# Mega-NTP-GPS-Shieldv3.net
KiCad netlist of a schematic drawn in EAGLE
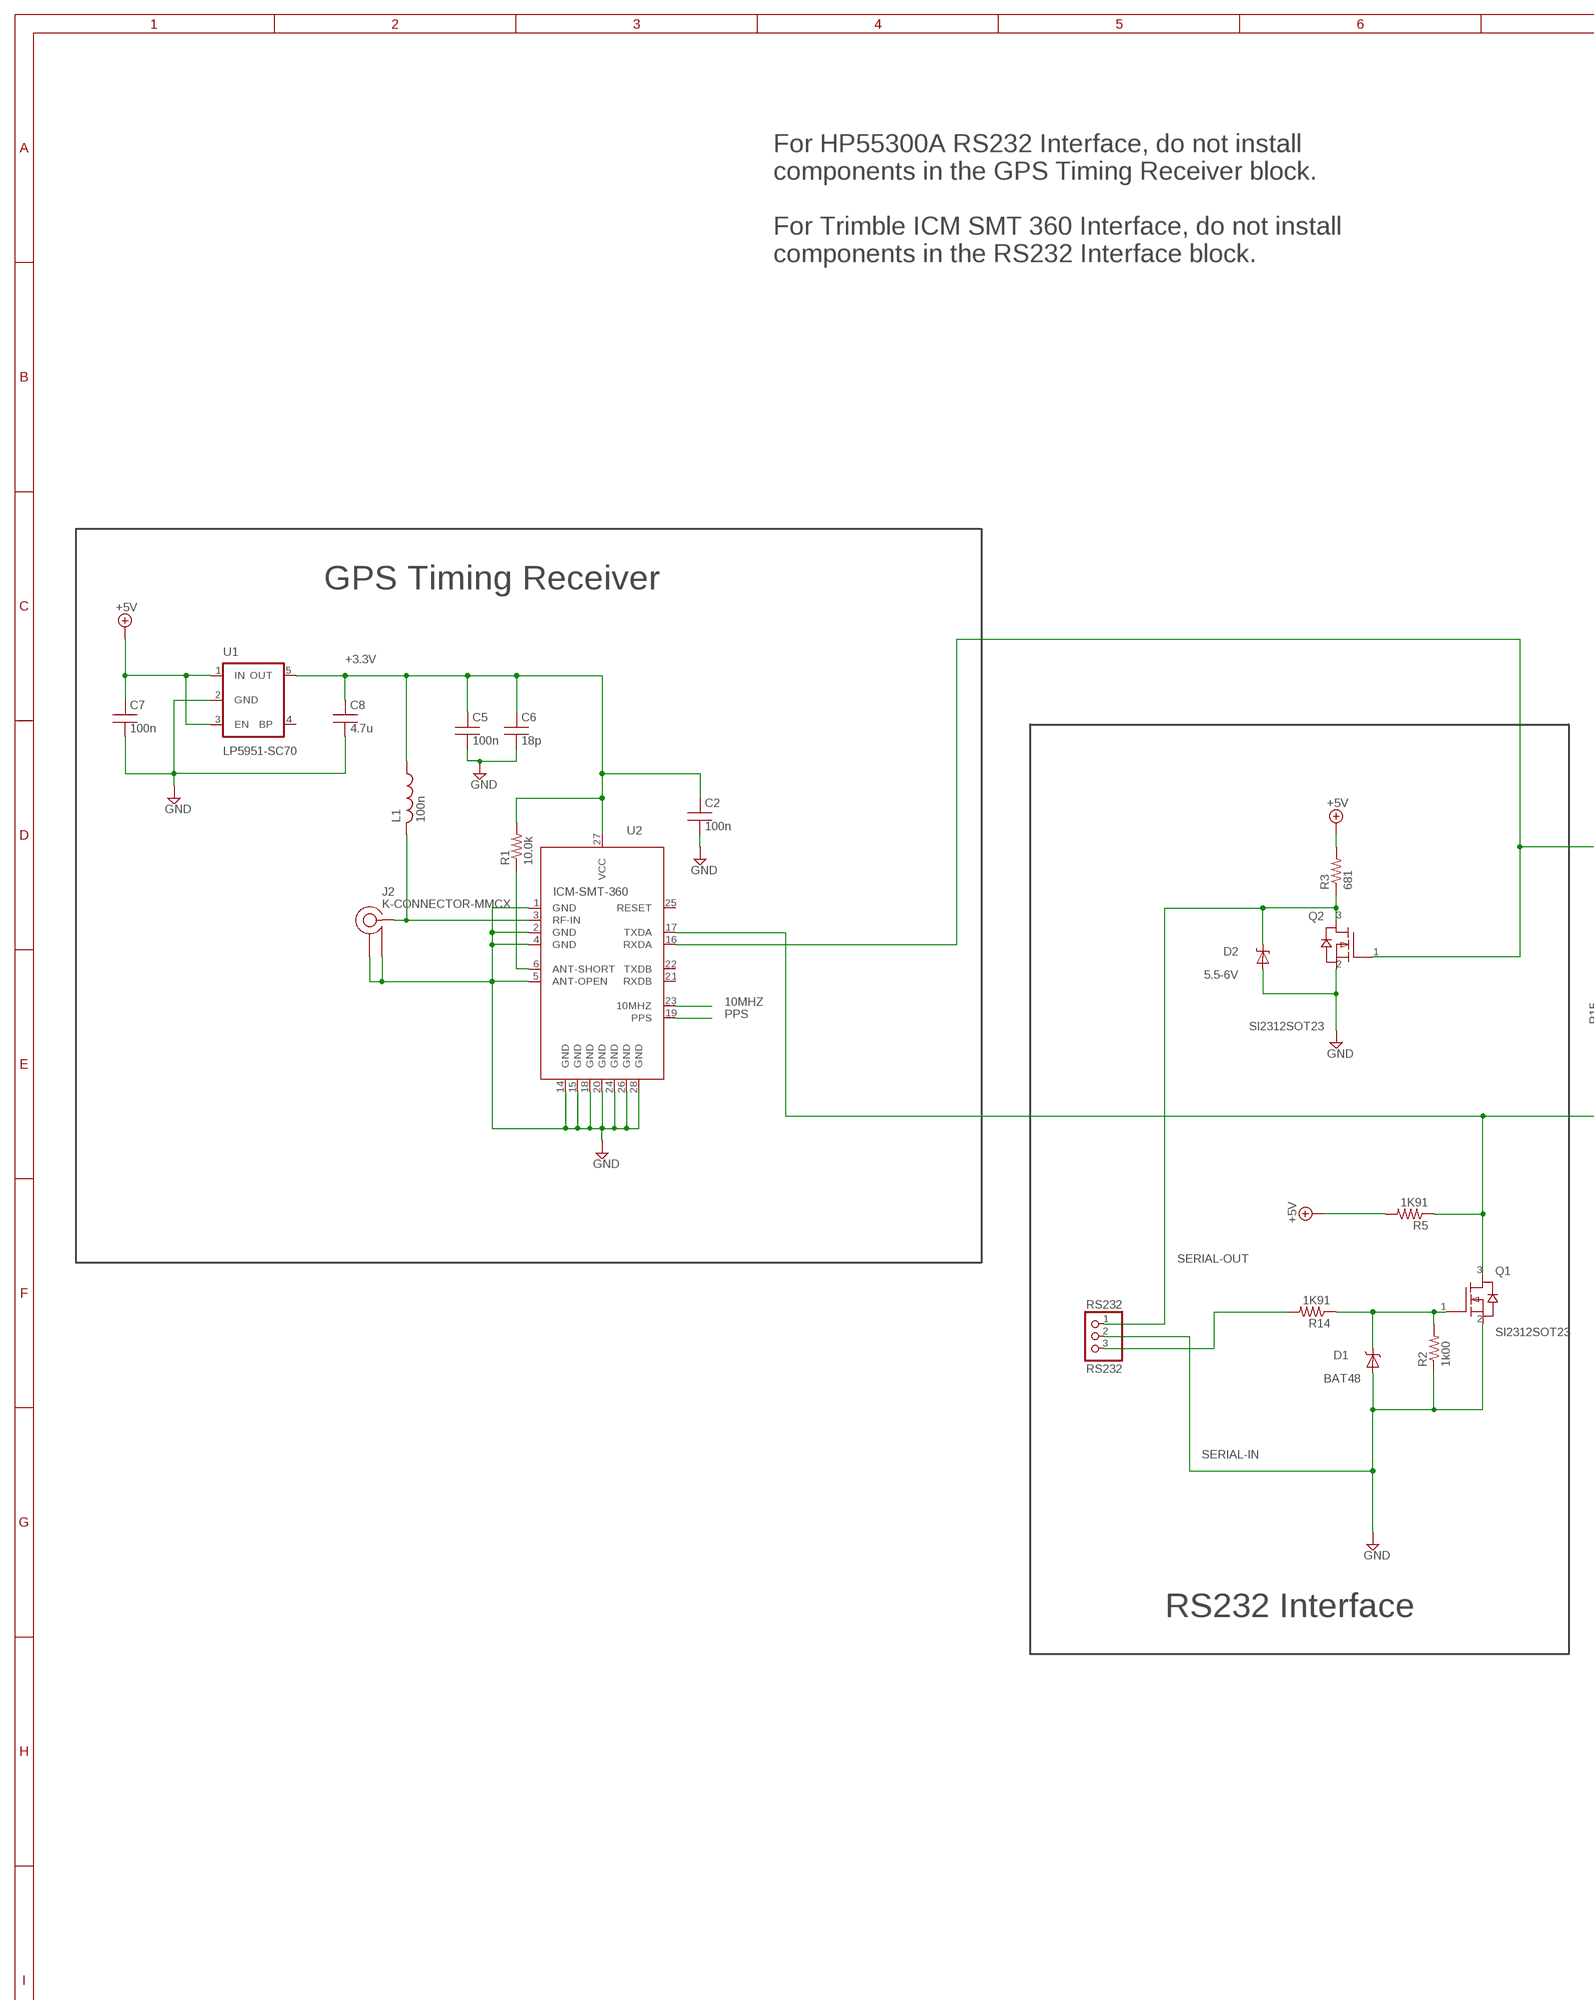
[diagram p0: schematic, sheet 1, part 1 of 2]
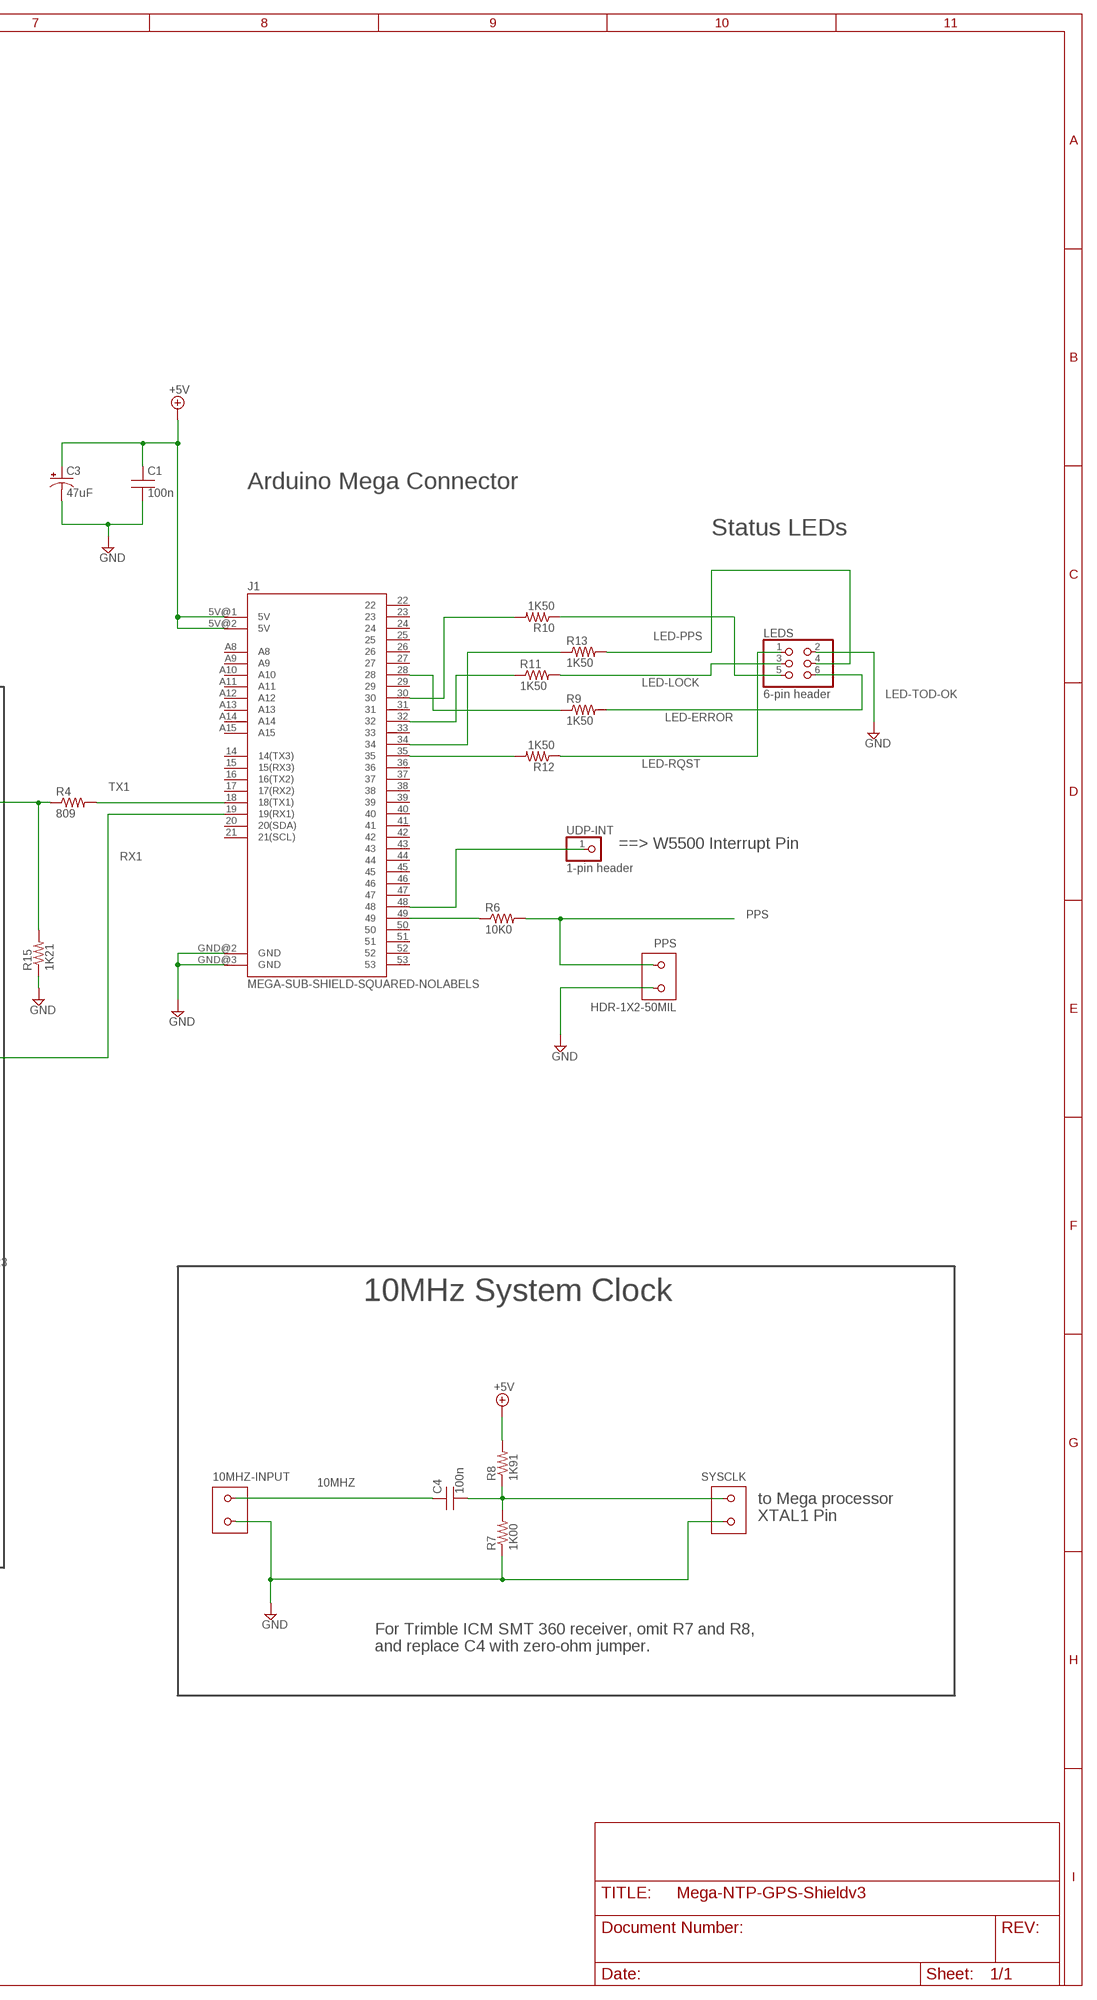
[diagram p1: schematic, sheet 1, part 2 of 2]

(export (version "E")
  (design (tool "Eeschema 10.0.6"))
  (components
    (comp (ref "10MHZ-INPUT")
      (value "HDR-1X2-100MIL")
      (footprint "eagle-import:1X02-100MIL")
      (libsource (lib "eagle-import") (part "HDR-1X2-100MIL"))
    )
    (comp (ref "C1")
      (value "100n")
      (footprint "eagle-import:AVX-0805")
      (fields (field (name "MFR") "AVX") (field (name "MPN") "0805(3/5)C104(J/K)ATxx"))
      (libsource (lib "eagle-import") (part "C-AVX-0805"))
    )
    (comp (ref "C2")
      (value "100n")
      (footprint "eagle-import:AVX-0805-NT")
      (fields (field (name "MFR") "AVX") (field (name "MPN") "0805(3/5)C104(J/K)ATxx"))
      (libsource (lib "eagle-import") (part "C-AVX-0805-NT"))
    )
    (comp (ref "C3")
      (value "47uF")
      (footprint "eagle-import:EIA3528")
      (fields (field (name "MFR") "Vishay/Sprague") (field (name "MPN") "TR3B476K010C0350"))
      (libsource (lib "eagle-import") (part "47UF-TANT"))
    )
    (comp (ref "C4")
      (value "100n")
      (footprint "eagle-import:AVX-0603")
      (fields (field (name "MFR") "AVX") (field (name "MPN") "0603(3/5)C104(J/K)ATxx"))
      (libsource (lib "eagle-import") (part "C-AVX-0603"))
    )
    (comp (ref "C5")
      (value "100n")
      (footprint "eagle-import:AVX-0603-NT")
      (fields (field (name "MFR") "AVX") (field (name "MPN") "0603(3/5)C104(J/K)ATxx"))
      (libsource (lib "eagle-import") (part "C-AVX-0603-NT"))
    )
    (comp (ref "C6")
      (value "18p")
      (footprint "eagle-import:AVX-0402-NT")
      (fields (field (name "MFR") "AVX") (field (name "MPN") "04025A180JATxx"))
      (libsource (lib "eagle-import") (part "C-AVX-0402-NT"))
    )
    (comp (ref "C7")
      (value "100n")
      (footprint "eagle-import:AVX-0603-NT")
      (fields (field (name "MFR") "AVX") (field (name "MPN") "0603(3/5)C104(J/K)ATxx"))
      (libsource (lib "eagle-import") (part "C-AVX-0603-NT"))
    )
    (comp (ref "C8")
      (value "4.7u")
      (footprint "eagle-import:AVX-0805-NT")
      (fields (field (name "MFR") "AVX") (field (name "MPN") "C0805YC475KATxx"))
      (libsource (lib "eagle-import") (part "C-AVX-0805-NT"))
    )
    (comp (ref "D1")
      (value "BAT48")
      (footprint "eagle-import:SOD-323")
      (libsource (lib "eagle-import") (part "DIODE-SCHOTTKY-SOD323"))
    )
    (comp (ref "D2")
      (value "5.5-6V")
      (footprint "eagle-import:SOD-323")
      (libsource (lib "eagle-import") (part "DIODE-ZENER-BZT52"))
    )
    (comp (ref "J1")
      (value "MEGA-SUB-SHIELD-SQUARED-NOLABELS")
      (footprint "eagle-import:MEGA-SUB-SHIELD-SQUARED-NOLABELS")
      (libsource (lib "eagle-import") (part "MEGA-SUB-SHIELD-SQUARED-NOLABELS"))
    )
    (comp (ref "J2")
      (value "K-CONNECTOR-MMCX")
      (footprint "eagle-import:MOLEX-MMCX-VERTICAL")
      (fields (field (name "MFR") "Molex") (field (name "MPN") "73415-206x"))
      (libsource (lib "eagle-import") (part "K-CONNECTOR-MMCX"))
    )
    (comp (ref "L1")
      (value "100n")
      (footprint "eagle-import:AVX-0603-NT")
      (fields (field (name "MFR") "Murata") (field (name "MPN") "LQW18ANR10J00"))
      (libsource (lib "eagle-import") (part "MURATA-LQW04A-LQW181-NT"))
    )
    (comp (ref "LEDS")
      (value "6-pin header")
      (footprint "eagle-import:2X03-50MIL")
      (libsource (lib "eagle-import") (part "HDR-2X3-ROW-SWAP-50MIL"))
    )
    (comp (ref "PPS")
      (value "HDR-1X2-50MIL")
      (footprint "eagle-import:1X02-50MIL")
      (libsource (lib "eagle-import") (part "HDR-1X2-50MIL"))
    )
    (comp (ref "Q1")
      (value "SI2312SOT23")
      (footprint "eagle-import:SOT23")
      (fields (field (name "MFR") "Siliconix") (field (name "MPN") "SI2312BDS"))
      (libsource (lib "eagle-import") (part "SI2312SOT23"))
    )
    (comp (ref "Q2")
      (value "SI2312SOT23")
      (footprint "eagle-import:SOT23")
      (fields (field (name "MFR") "Siliconix") (field (name "MPN") "SI2312BDS"))
      (libsource (lib "eagle-import") (part "SI2312SOT23"))
    )
    (comp (ref "R1")
      (value "10.0k")
      (footprint "eagle-import:AVX-0603")
      (fields (field (name "MFR") "Vishay/Dale") (field (name "MPN") "CRCW060310.0kFKxx"))
      (libsource (lib "eagle-import") (part "R-AVX-0603"))
    )
    (comp (ref "R2")
      (value "1k00")
      (footprint "eagle-import:AVX-0603-NT")
      (fields (field (name "MFR") "Vishay/Dale") (field (name "MPN") "CRCW06034K02FKxx"))
      (libsource (lib "eagle-import") (part "R-AVX-0603-NT"))
    )
    (comp (ref "R3")
      (value "681")
      (footprint "eagle-import:AVX-0603")
      (fields (field (name "MFR") "Vishay/Dale") (field (name "MPN") "CRCW0603DNP (681)FKxx"))
      (libsource (lib "eagle-import") (part "R-AVX-0603"))
    )
    (comp (ref "R4")
      (value "809")
      (footprint "eagle-import:AVX-0603")
      (fields (field (name "MFR") "Vishay/Dale") (field (name "MPN") "CRCW06031K91FKxx"))
      (libsource (lib "eagle-import") (part "R-AVX-0603"))
    )
    (comp (ref "R5")
      (value "1K91")
      (footprint "eagle-import:AVX-0603")
      (fields (field (name "MFR") "Vishay/Dale") (field (name "MPN") "CRCW06031K91FKxx"))
      (libsource (lib "eagle-import") (part "R-AVX-0603"))
    )
    (comp (ref "R6")
      (value "10K0")
      (footprint "eagle-import:AVX-0603")
      (fields (field (name "MFR") "Vishay/Dale") (field (name "MPN") "CRCW060310K0FKxx"))
      (libsource (lib "eagle-import") (part "R-AVX-0603"))
    )
    (comp (ref "R7")
      (value "1K00")
      (footprint "eagle-import:AVX-0603")
      (fields (field (name "MFR") "Vishay/Dale") (field (name "MPN") "CRCW06031K91FKxx"))
      (libsource (lib "eagle-import") (part "R-AVX-0603"))
    )
    (comp (ref "R8")
      (value "1K91")
      (footprint "eagle-import:AVX-0603")
      (fields (field (name "MFR") "Vishay/Dale") (field (name "MPN") "CRCW06031K91FKxx"))
      (libsource (lib "eagle-import") (part "R-AVX-0603"))
    )
    (comp (ref "R9")
      (value "1K50")
      (footprint "eagle-import:AVX-0603")
      (fields (field (name "MFR") "Vishay/Dale") (field (name "MPN") "CRCW06031K50FKxx"))
      (libsource (lib "eagle-import") (part "R-AVX-0603"))
    )
    (comp (ref "R10")
      (value "1K50")
      (footprint "eagle-import:AVX-0603")
      (fields (field (name "MFR") "Vishay/Dale") (field (name "MPN") "CRCW06031K50FKxx"))
      (libsource (lib "eagle-import") (part "R-AVX-0603"))
    )
    (comp (ref "R11")
      (value "1K50")
      (footprint "eagle-import:AVX-0603")
      (fields (field (name "MFR") "Vishay/Dale") (field (name "MPN") "CRCW06031K50FKxx"))
      (libsource (lib "eagle-import") (part "R-AVX-0603"))
    )
    (comp (ref "R12")
      (value "1K50")
      (footprint "eagle-import:AVX-0603")
      (fields (field (name "MFR") "Vishay/Dale") (field (name "MPN") "CRCW06031K50FKxx"))
      (libsource (lib "eagle-import") (part "R-AVX-0603"))
    )
    (comp (ref "R13")
      (value "1K50")
      (footprint "eagle-import:AVX-0603")
      (fields (field (name "MFR") "Vishay/Dale") (field (name "MPN") "CRCW06031K50FKxx"))
      (libsource (lib "eagle-import") (part "R-AVX-0603"))
    )
    (comp (ref "R14")
      (value "1K91")
      (footprint "eagle-import:AVX-0603")
      (fields (field (name "MFR") "Vishay/Dale") (field (name "MPN") "CRCW06034K02FKxx"))
      (libsource (lib "eagle-import") (part "R-AVX-0603"))
    )
    (comp (ref "R15")
      (value "1K21")
      (footprint "eagle-import:AVX-0603-NT")
      (fields (field (name "MFR") "Vishay/Dale") (field (name "MPN") "CRCW06034K02FKxx"))
      (libsource (lib "eagle-import") (part "R-AVX-0603-NT"))
    )
    (comp (ref "RS232")
      (value "RS232")
      (footprint "eagle-import:1X03-100MIL")
      (libsource (lib "eagle-import") (part "HDR-1X3-ALL-SWAP-100-MIL"))
    )
    (comp (ref "SYSCLK")
      (value "HDR-1X2-100MIL")
      (footprint "eagle-import:1X02-100MIL")
      (libsource (lib "eagle-import") (part "HDR-1X2-100MIL"))
    )
    (comp (ref "U1")
      (value "LP5951-SC70")
      (footprint "eagle-import:SC70")
      (fields (field (name "MFR") "TI") (field (name "MPN") "LP5951MG-3.3/NOPB"))
      (libsource (lib "eagle-import") (part "V_REG_LDOSMD2"))
    )
    (comp (ref "U2")
      (value "ICM-SMT-360")
      (footprint "eagle-import:TRIMBLE-ICM-SMT-360")
      (fields (field (name "MFR") "Trimble"))
      (libsource (lib "eagle-import") (part "TRIMBLE-ICM-SMT-360-GPS-TIMING-MODULE"))
    )
    (comp (ref "UDP-INT")
      (value "1-pin header")
      (footprint "eagle-import:1X01")
      (libsource (lib "eagle-import") (part "PINHD-1X1"))
    )
  )
  (nets
    (net (code "1") (name "+5V") (class "Default")
      (node (ref "C1") (pin "1") (pinfunction "1_1") (pintype "passive"))
      (node (ref "C3") (pin "A") (pinfunction "+_A") (pintype "passive"))
      (node (ref "C7") (pin "1") (pinfunction "1_1") (pintype "passive"))
      (node (ref "J1") (pin "5V@1") (pinfunction "5V_5V@1") (pintype "bidirectional"))
      (node (ref "J1") (pin "5V@2") (pinfunction "5V_5V@2") (pintype "bidirectional"))
      (node (ref "R3") (pin "2") (pinfunction "2_2") (pintype "passive"))
      (node (ref "R5") (pin "2") (pinfunction "2_2") (pintype "passive"))
      (node (ref "R8") (pin "2") (pinfunction "2_2") (pintype "passive"))
      (node (ref "U1") (pin "1") (pinfunction "IN_1") (pintype "input"))
      (node (ref "U1") (pin "3") (pinfunction "EN_3") (pintype "input"))
    )
    (net (code "2") (name "/+3.3V") (class "Default")
      (node (ref "C2") (pin "1") (pinfunction "1_1") (pintype "passive"))
      (node (ref "C5") (pin "1") (pinfunction "1_1") (pintype "passive"))
      (node (ref "C6") (pin "1") (pinfunction "1_1") (pintype "passive"))
      (node (ref "C8") (pin "1") (pinfunction "1_1") (pintype "passive"))
      (node (ref "L1") (pin "1") (pinfunction "1_1") (pintype "passive"))
      (node (ref "R1") (pin "2") (pinfunction "2_2") (pintype "passive"))
      (node (ref "U1") (pin "5") (pinfunction "OUT_5") (pintype "passive"))
      (node (ref "U2") (pin "27") (pinfunction "VCC_27") (pintype "passive"))
    )
    (net (code "3") (name "/10MHZ") (class "Default")
      (node (ref "10MHZ-INPUT") (pin "1") (pinfunction "1_1") (pintype "passive"))
      (node (ref "C4") (pin "1") (pinfunction "1_1") (pintype "passive"))
      (node (ref "U2") (pin "23") (pinfunction "10MHZ_23") (pintype "output"))
    )
    (net (code "4") (name "/LED-ERROR") (class "Default")
      (node (ref "LEDS") (pin "6") (pinfunction "6_6") (pintype "passive"))
      (node (ref "R9") (pin "2") (pinfunction "2_2") (pintype "passive"))
    )
    (net (code "5") (name "/LED-LOCK") (class "Default")
      (node (ref "LEDS") (pin "3") (pinfunction "3_3") (pintype "passive"))
      (node (ref "R11") (pin "2") (pinfunction "2_2") (pintype "passive"))
    )
    (net (code "6") (name "/LED-PPS") (class "Default")
      (node (ref "LEDS") (pin "4") (pinfunction "4_4") (pintype "passive"))
      (node (ref "R13") (pin "2") (pinfunction "2_2") (pintype "passive"))
    )
    (net (code "7") (name "/LED-RQST") (class "Default")
      (node (ref "LEDS") (pin "1") (pinfunction "1_1") (pintype "passive"))
      (node (ref "R12") (pin "1") (pinfunction "1_1") (pintype "passive"))
    )
    (net (code "8") (name "/LED-TOD-OK") (class "Default")
      (node (ref "LEDS") (pin "5") (pinfunction "5_5") (pintype "passive"))
      (node (ref "R10") (pin "1") (pinfunction "1_1") (pintype "passive"))
    )
    (net (code "9") (name "/PPS") (class "Default")
      (node (ref "PPS") (pin "1") (pinfunction "1_1") (pintype "passive"))
      (node (ref "R6") (pin "2") (pinfunction "2_2") (pintype "passive"))
      (node (ref "U2") (pin "19") (pinfunction "PPS_19") (pintype "output"))
    )
    (net (code "10") (name "/RX1") (class "Default")
      (node (ref "J1") (pin "19") (pinfunction "19(RX1)_19") (pintype "bidirectional"))
      (node (ref "Q1") (pin "3") (pinfunction "D_3") (pintype "passive"))
      (node (ref "R5") (pin "1") (pinfunction "1_1") (pintype "passive"))
      (node (ref "U2") (pin "17") (pinfunction "TXDA_17") (pintype "bidirectional"))
    )
    (net (code "11") (name "/SERIAL-IN") (class "Default")
      (node (ref "R14") (pin "2") (pinfunction "2_2") (pintype "passive"))
      (node (ref "RS232") (pin "3") (pinfunction "3_3") (pintype "passive"))
    )
    (net (code "12") (name "/SERIAL-OUT") (class "Default")
      (node (ref "D2") (pin "1") (pinfunction "C_1") (pintype "passive"))
      (node (ref "Q2") (pin "3") (pinfunction "D_3") (pintype "passive"))
      (node (ref "R3") (pin "1") (pinfunction "1_1") (pintype "passive"))
      (node (ref "RS232") (pin "1") (pinfunction "1_1") (pintype "passive"))
    )
    (net (code "13") (name "/TX1") (class "Default")
      (node (ref "J1") (pin "18") (pinfunction "18(TX1)_18") (pintype "bidirectional"))
      (node (ref "R4") (pin "2") (pinfunction "2_2") (pintype "passive"))
    )
    (net (code "14") (name "GND") (class "Default")
      (node (ref "10MHZ-INPUT") (pin "2") (pinfunction "2_2") (pintype "passive"))
      (node (ref "C1") (pin "2") (pinfunction "2_2") (pintype "passive"))
      (node (ref "C2") (pin "2") (pinfunction "2_2") (pintype "passive"))
      (node (ref "C3") (pin "C") (pinfunction "-_C") (pintype "passive"))
      (node (ref "C5") (pin "2") (pinfunction "2_2") (pintype "passive"))
      (node (ref "C6") (pin "2") (pinfunction "2_2") (pintype "passive"))
      (node (ref "C7") (pin "2") (pinfunction "2_2") (pintype "passive"))
      (node (ref "C8") (pin "2") (pinfunction "2_2") (pintype "passive"))
      (node (ref "D1") (pin "2") (pinfunction "A_2") (pintype "passive"))
      (node (ref "D2") (pin "2") (pinfunction "A_2") (pintype "passive"))
      (node (ref "J1") (pin "GND@2") (pinfunction "GND_GND@2") (pintype "bidirectional"))
      (node (ref "J1") (pin "GND@3") (pinfunction "GND_GND@3") (pintype "bidirectional"))
      (node (ref "J2") (pin "GND1") (pinfunction "GND1_GND1") (pintype "passive"))
      (node (ref "J2") (pin "GND2") (pinfunction "GND2_GND2") (pintype "passive"))
      (node (ref "LEDS") (pin "2") (pinfunction "2_2") (pintype "passive"))
      (node (ref "PPS") (pin "2") (pinfunction "2_2") (pintype "passive"))
      (node (ref "Q1") (pin "2") (pinfunction "S_2") (pintype "passive"))
      (node (ref "Q2") (pin "2") (pinfunction "S_2") (pintype "passive"))
      (node (ref "R15") (pin "1") (pinfunction "1_1") (pintype "passive"))
      (node (ref "R2") (pin "1") (pinfunction "1_1") (pintype "passive"))
      (node (ref "R7") (pin "1") (pinfunction "1_1") (pintype "passive"))
      (node (ref "RS232") (pin "2") (pinfunction "2_2") (pintype "passive"))
      (node (ref "SYSCLK") (pin "2") (pinfunction "2_2") (pintype "passive"))
      (node (ref "U1") (pin "2") (pinfunction "GND_2") (pintype "input"))
      (node (ref "U2") (pin "1") (pinfunction "GND_1") (pintype "power_in"))
      (node (ref "U2") (pin "14") (pinfunction "GND_14") (pintype "power_in"))
      (node (ref "U2") (pin "15") (pinfunction "GND_15") (pintype "power_in"))
      (node (ref "U2") (pin "18") (pinfunction "GND_18") (pintype "power_in"))
      (node (ref "U2") (pin "2") (pinfunction "GND_2") (pintype "power_in"))
      (node (ref "U2") (pin "20") (pinfunction "GND_20") (pintype "power_in"))
      (node (ref "U2") (pin "24") (pinfunction "GND_24") (pintype "power_in"))
      (node (ref "U2") (pin "26") (pinfunction "GND_26") (pintype "power_in"))
      (node (ref "U2") (pin "28") (pinfunction "GND_28") (pintype "power_in"))
      (node (ref "U2") (pin "4") (pinfunction "GND_4") (pintype "power_in"))
      (node (ref "U2") (pin "5") (pinfunction "ANT-OPEN_5") (pintype "bidirectional"))
    )
    (net (code "15") (name "Net-(C4-Pad2)") (class "Default")
      (node (ref "C4") (pin "2") (pinfunction "2_2") (pintype "passive"))
      (node (ref "R7") (pin "2") (pinfunction "2_2") (pintype "passive"))
      (node (ref "R8") (pin "1") (pinfunction "1_1") (pintype "passive"))
      (node (ref "SYSCLK") (pin "1") (pinfunction "1_1") (pintype "passive"))
    )
    (net (code "16") (name "Net-(D1-C)") (class "Default")
      (node (ref "D1") (pin "1") (pinfunction "C_1") (pintype "passive"))
      (node (ref "Q1") (pin "1") (pinfunction "G_1") (pintype "passive"))
      (node (ref "R14") (pin "1") (pinfunction "1_1") (pintype "passive"))
      (node (ref "R2") (pin "2") (pinfunction "2_2") (pintype "passive"))
    )
    (net (code "17") (name "Net-(J1-Pad28)") (class "Default")
      (node (ref "J1") (pin "28") (pinfunction "28_28") (pintype "bidirectional"))
      (node (ref "R9") (pin "1") (pinfunction "1_1") (pintype "passive"))
    )
    (net (code "18") (name "Net-(J1-Pad30)") (class "Default")
      (node (ref "J1") (pin "30") (pinfunction "30_30") (pintype "bidirectional"))
      (node (ref "R10") (pin "2") (pinfunction "2_2") (pintype "passive"))
    )
    (net (code "19") (name "Net-(J1-Pad32)") (class "Default")
      (node (ref "J1") (pin "32") (pinfunction "32_32") (pintype "bidirectional"))
      (node (ref "R11") (pin "1") (pinfunction "1_1") (pintype "passive"))
    )
    (net (code "20") (name "Net-(J1-Pad34)") (class "Default")
      (node (ref "J1") (pin "34") (pinfunction "34_34") (pintype "bidirectional"))
      (node (ref "R13") (pin "1") (pinfunction "1_1") (pintype "passive"))
    )
    (net (code "21") (name "Net-(J1-Pad35)") (class "Default")
      (node (ref "J1") (pin "35") (pinfunction "35_35") (pintype "bidirectional"))
      (node (ref "R12") (pin "2") (pinfunction "2_2") (pintype "passive"))
    )
    (net (code "22") (name "Net-(J1-Pad48)") (class "Default")
      (node (ref "J1") (pin "48") (pinfunction "48_48") (pintype "bidirectional"))
      (node (ref "UDP-INT") (pin "1") (pinfunction "1_1") (pintype "passive"))
    )
    (net (code "23") (name "Net-(J1-Pad49)") (class "Default")
      (node (ref "J1") (pin "49") (pinfunction "49_49") (pintype "bidirectional"))
      (node (ref "R6") (pin "1") (pinfunction "1_1") (pintype "passive"))
    )
    (net (code "24") (name "Net-(J2-1)") (class "Default")
      (node (ref "J2") (pin "CENTER") (pinfunction "1_CENTER") (pintype "passive"))
      (node (ref "L1") (pin "2") (pinfunction "2_2") (pintype "passive"))
      (node (ref "U2") (pin "3") (pinfunction "RF-IN_3") (pintype "passive"))
    )
    (net (code "25") (name "Net-(Q2-G)") (class "Default")
      (node (ref "Q2") (pin "1") (pinfunction "G_1") (pintype "passive"))
      (node (ref "R15") (pin "2") (pinfunction "2_2") (pintype "passive"))
      (node (ref "R4") (pin "1") (pinfunction "1_1") (pintype "passive"))
      (node (ref "U2") (pin "16") (pinfunction "RXDA_16") (pintype "bidirectional"))
    )
    (net (code "26") (name "Net-(U2-ANT-SHORT)") (class "Default")
      (node (ref "R1") (pin "1") (pinfunction "1_1") (pintype "passive"))
      (node (ref "U2") (pin "6") (pinfunction "ANT-SHORT_6") (pintype "bidirectional"))
    )
    (net (code "27") (name "unconnected-(J1-14(TX3)-Pad14)") (class "Default")
      (node (ref "J1") (pin "14") (pinfunction "14(TX3)_14") (pintype "bidirectional"))
    )
    (net (code "28") (name "unconnected-(J1-15(RX3)-Pad15)") (class "Default")
      (node (ref "J1") (pin "15") (pinfunction "15(RX3)_15") (pintype "bidirectional"))
    )
    (net (code "29") (name "unconnected-(J1-16(TX2)-Pad16)") (class "Default")
      (node (ref "J1") (pin "16") (pinfunction "16(TX2)_16") (pintype "bidirectional"))
    )
    (net (code "30") (name "unconnected-(J1-17(RX2)-Pad17)") (class "Default")
      (node (ref "J1") (pin "17") (pinfunction "17(RX2)_17") (pintype "bidirectional"))
    )
    (net (code "31") (name "unconnected-(J1-20(SDA)-Pad20)") (class "Default")
      (node (ref "J1") (pin "20") (pinfunction "20(SDA)_20") (pintype "bidirectional"))
    )
    (net (code "32") (name "unconnected-(J1-21(SCL)-Pad21)") (class "Default")
      (node (ref "J1") (pin "21") (pinfunction "21(SCL)_21") (pintype "bidirectional"))
    )
    (net (code "33") (name "unconnected-(J1-Pad22)") (class "Default")
      (node (ref "J1") (pin "22") (pinfunction "22_22") (pintype "bidirectional"))
    )
    (net (code "34") (name "unconnected-(J1-Pad23)") (class "Default")
      (node (ref "J1") (pin "23") (pinfunction "23_23") (pintype "bidirectional"))
    )
    (net (code "35") (name "unconnected-(J1-Pad24)") (class "Default")
      (node (ref "J1") (pin "24") (pinfunction "24_24") (pintype "bidirectional"))
    )
    (net (code "36") (name "unconnected-(J1-Pad25)") (class "Default")
      (node (ref "J1") (pin "25") (pinfunction "25_25") (pintype "bidirectional"))
    )
    (net (code "37") (name "unconnected-(J1-Pad26)") (class "Default")
      (node (ref "J1") (pin "26") (pinfunction "26_26") (pintype "bidirectional"))
    )
    (net (code "38") (name "unconnected-(J1-Pad27)") (class "Default")
      (node (ref "J1") (pin "27") (pinfunction "27_27") (pintype "bidirectional"))
    )
    (net (code "39") (name "unconnected-(J1-Pad29)") (class "Default")
      (node (ref "J1") (pin "29") (pinfunction "29_29") (pintype "bidirectional"))
    )
    (net (code "40") (name "unconnected-(J1-Pad31)") (class "Default")
      (node (ref "J1") (pin "31") (pinfunction "31_31") (pintype "bidirectional"))
    )
    (net (code "41") (name "unconnected-(J1-Pad33)") (class "Default")
      (node (ref "J1") (pin "33") (pinfunction "33_33") (pintype "bidirectional"))
    )
    (net (code "42") (name "unconnected-(J1-Pad36)") (class "Default")
      (node (ref "J1") (pin "36") (pinfunction "36_36") (pintype "bidirectional"))
    )
    (net (code "43") (name "unconnected-(J1-Pad37)") (class "Default")
      (node (ref "J1") (pin "37") (pinfunction "37_37") (pintype "bidirectional"))
    )
    (net (code "44") (name "unconnected-(J1-Pad38)") (class "Default")
      (node (ref "J1") (pin "38") (pinfunction "38_38") (pintype "bidirectional"))
    )
    (net (code "45") (name "unconnected-(J1-Pad39)") (class "Default")
      (node (ref "J1") (pin "39") (pinfunction "39_39") (pintype "bidirectional"))
    )
    (net (code "46") (name "unconnected-(J1-Pad40)") (class "Default")
      (node (ref "J1") (pin "40") (pinfunction "40_40") (pintype "bidirectional"))
    )
    (net (code "47") (name "unconnected-(J1-Pad41)") (class "Default")
      (node (ref "J1") (pin "41") (pinfunction "41_41") (pintype "bidirectional"))
    )
    (net (code "48") (name "unconnected-(J1-Pad42)") (class "Default")
      (node (ref "J1") (pin "42") (pinfunction "42_42") (pintype "bidirectional"))
    )
    (net (code "49") (name "unconnected-(J1-Pad43)") (class "Default")
      (node (ref "J1") (pin "43") (pinfunction "43_43") (pintype "bidirectional"))
    )
    (net (code "50") (name "unconnected-(J1-Pad44)") (class "Default")
      (node (ref "J1") (pin "44") (pinfunction "44_44") (pintype "bidirectional"))
    )
    (net (code "51") (name "unconnected-(J1-Pad45)") (class "Default")
      (node (ref "J1") (pin "45") (pinfunction "45_45") (pintype "bidirectional"))
    )
    (net (code "52") (name "unconnected-(J1-Pad46)") (class "Default")
      (node (ref "J1") (pin "46") (pinfunction "46_46") (pintype "bidirectional"))
    )
    (net (code "53") (name "unconnected-(J1-Pad47)") (class "Default")
      (node (ref "J1") (pin "47") (pinfunction "47_47") (pintype "bidirectional"))
    )
    (net (code "54") (name "unconnected-(J1-Pad50)") (class "Default")
      (node (ref "J1") (pin "50") (pinfunction "50_50") (pintype "bidirectional"))
    )
    (net (code "55") (name "unconnected-(J1-Pad51)") (class "Default")
      (node (ref "J1") (pin "51") (pinfunction "51_51") (pintype "bidirectional"))
    )
    (net (code "56") (name "unconnected-(J1-Pad52)") (class "Default")
      (node (ref "J1") (pin "52") (pinfunction "52_52") (pintype "bidirectional"))
    )
    (net (code "57") (name "unconnected-(J1-Pad53)") (class "Default")
      (node (ref "J1") (pin "53") (pinfunction "53_53") (pintype "bidirectional"))
    )
    (net (code "58") (name "unconnected-(J1-PadA8)") (class "Default")
      (node (ref "J1") (pin "A8") (pinfunction "A8_A8") (pintype "bidirectional"))
    )
    (net (code "59") (name "unconnected-(J1-PadA9)") (class "Default")
      (node (ref "J1") (pin "A9") (pinfunction "A9_A9") (pintype "bidirectional"))
    )
    (net (code "60") (name "unconnected-(J1-PadA10)") (class "Default")
      (node (ref "J1") (pin "A10") (pinfunction "A10_A10") (pintype "bidirectional"))
    )
    (net (code "61") (name "unconnected-(J1-PadA11)") (class "Default")
      (node (ref "J1") (pin "A11") (pinfunction "A11_A11") (pintype "bidirectional"))
    )
    (net (code "62") (name "unconnected-(J1-PadA12)") (class "Default")
      (node (ref "J1") (pin "A12") (pinfunction "A12_A12") (pintype "bidirectional"))
    )
    (net (code "63") (name "unconnected-(J1-PadA13)") (class "Default")
      (node (ref "J1") (pin "A13") (pinfunction "A13_A13") (pintype "bidirectional"))
    )
    (net (code "64") (name "unconnected-(J1-PadA14)") (class "Default")
      (node (ref "J1") (pin "A14") (pinfunction "A14_A14") (pintype "bidirectional"))
    )
    (net (code "65") (name "unconnected-(J1-PadA15)") (class "Default")
      (node (ref "J1") (pin "A15") (pinfunction "A15_A15") (pintype "bidirectional"))
    )
    (net (code "66") (name "unconnected-(U1-BP-Pad4)") (class "Default")
      (node (ref "U1") (pin "4") (pinfunction "BP_4") (pintype "passive"))
    )
    (net (code "67") (name "unconnected-(U2-RESET-Pad25)") (class "Default")
      (node (ref "U2") (pin "25") (pinfunction "RESET_25") (pintype "bidirectional"))
    )
    (net (code "68") (name "unconnected-(U2-RXDB-Pad21)") (class "Default")
      (node (ref "U2") (pin "21") (pinfunction "RXDB_21") (pintype "bidirectional"))
    )
    (net (code "69") (name "unconnected-(U2-TXDB-Pad22)") (class "Default")
      (node (ref "U2") (pin "22") (pinfunction "TXDB_22") (pintype "bidirectional"))
    )
  )
)
